# OpAmp.net
KiCad netlist of a schematic drawn in Altium Designer
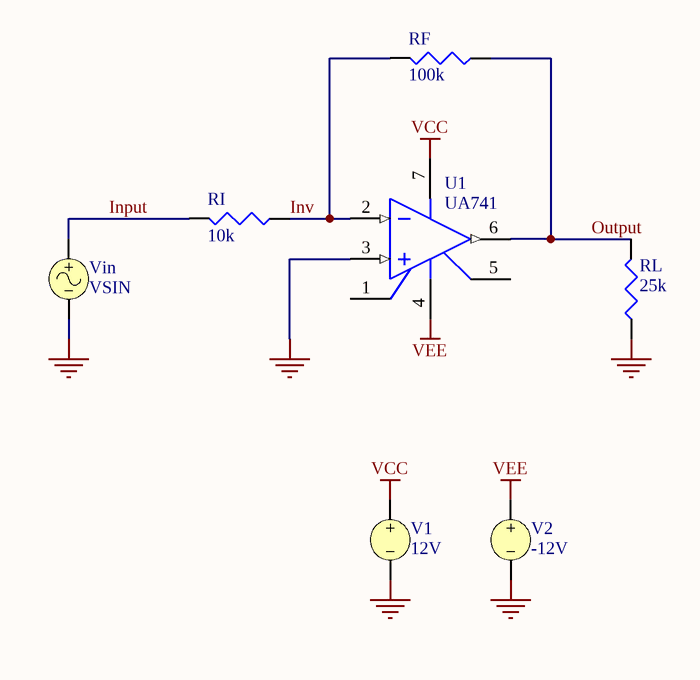
[diagram p0: OpAmp.schdoc]

(export (version "E")
  (design (tool "Eeschema 10.0.6"))
  (components
    (comp (ref "RF") (value "100k") (description "Resistor") (libsource (lib "") (part "RES_1")))
    (comp (ref "RI") (value "10k") (description "Resistor") (libsource (lib "") (part "RES_1")))
    (comp (ref "RL") (value "25k") (description "Resistor") (libsource (lib "*") (part "RES")))
    (comp (ref "U1")
      (value "UA741")
      (description "General-Purpose Operational Amplifier")
      (libsource (lib "*") (part "UA741"))
    )
    (comp (ref "V1") (value "12V") (description "Voltage Source") (libsource (lib "*") (part "VSRC")))
    (comp (ref "V2") (value "-12V") (description "Voltage Source") (libsource (lib "*") (part "VSRC")))
    (comp (ref "Vin")
      (value "VSIN")
      (description "Sinusoidal Voltage Source")
      (libsource (lib "*") (part "VSIN"))
    )
  )
  (nets
    (net (code "1") (name "/Input") (class "Default")
      (node (ref "RI") (pin "1") (pinfunction "TOP_1") (pintype "passive"))
      (node (ref "Vin") (pin "1") (pinfunction "1_1") (pintype "passive"))
    )
    (net (code "2") (name "/Inv") (class "Default")
      (node (ref "RF") (pin "1") (pinfunction "TOP_1") (pintype "passive"))
      (node (ref "RI") (pin "2") (pinfunction "BOT_2") (pintype "passive"))
      (node (ref "U1") (pin "2") (pinfunction "-IN_2") (pintype "input"))
    )
    (net (code "3") (name "/Output") (class "Default")
      (node (ref "RF") (pin "2") (pinfunction "BOT_2") (pintype "passive"))
      (node (ref "RL") (pin "1") (pinfunction "TOP_1") (pintype "passive"))
      (node (ref "U1") (pin "6") (pinfunction "OUT_6") (pintype "output"))
    )
    (net (code "4") (name "GND") (class "Default")
      (node (ref "RL") (pin "2") (pinfunction "BOT_2") (pintype "passive"))
      (node (ref "U1") (pin "3") (pinfunction "+IN_3") (pintype "input"))
      (node (ref "V1") (pin "2") (pinfunction "2_2") (pintype "passive"))
      (node (ref "V2") (pin "2") (pinfunction "2_2") (pintype "passive"))
      (node (ref "Vin") (pin "2") (pinfunction "2_2") (pintype "passive"))
    )
    (net (code "5") (name "VCC") (class "Default")
      (node (ref "U1") (pin "7") (pinfunction "V+_7") (pintype "power_in"))
      (node (ref "V1") (pin "1") (pinfunction "1_1") (pintype "passive"))
    )
    (net (code "6") (name "VEE") (class "Default")
      (node (ref "U1") (pin "4") (pinfunction "V-_4") (pintype "power_in"))
      (node (ref "V2") (pin "1") (pinfunction "1_1") (pintype "passive"))
    )
    (net (code "7") (name "unconnected-(U1-OFFSET_NULL_1-Pad1)") (class "Default")
      (node (ref "U1") (pin "1") (pinfunction "OFFSET_NULL_1_1") (pintype "passive"))
    )
    (net (code "8") (name "unconnected-(U1-OFFSET_NULL_2-Pad5)") (class "Default")
      (node (ref "U1") (pin "5") (pinfunction "OFFSET_NULL_2_5") (pintype "passive"))
    )
  )
)
